# DC_MotorDriver_2Channel.net
KiCad netlist of a schematic drawn in Altium Designer
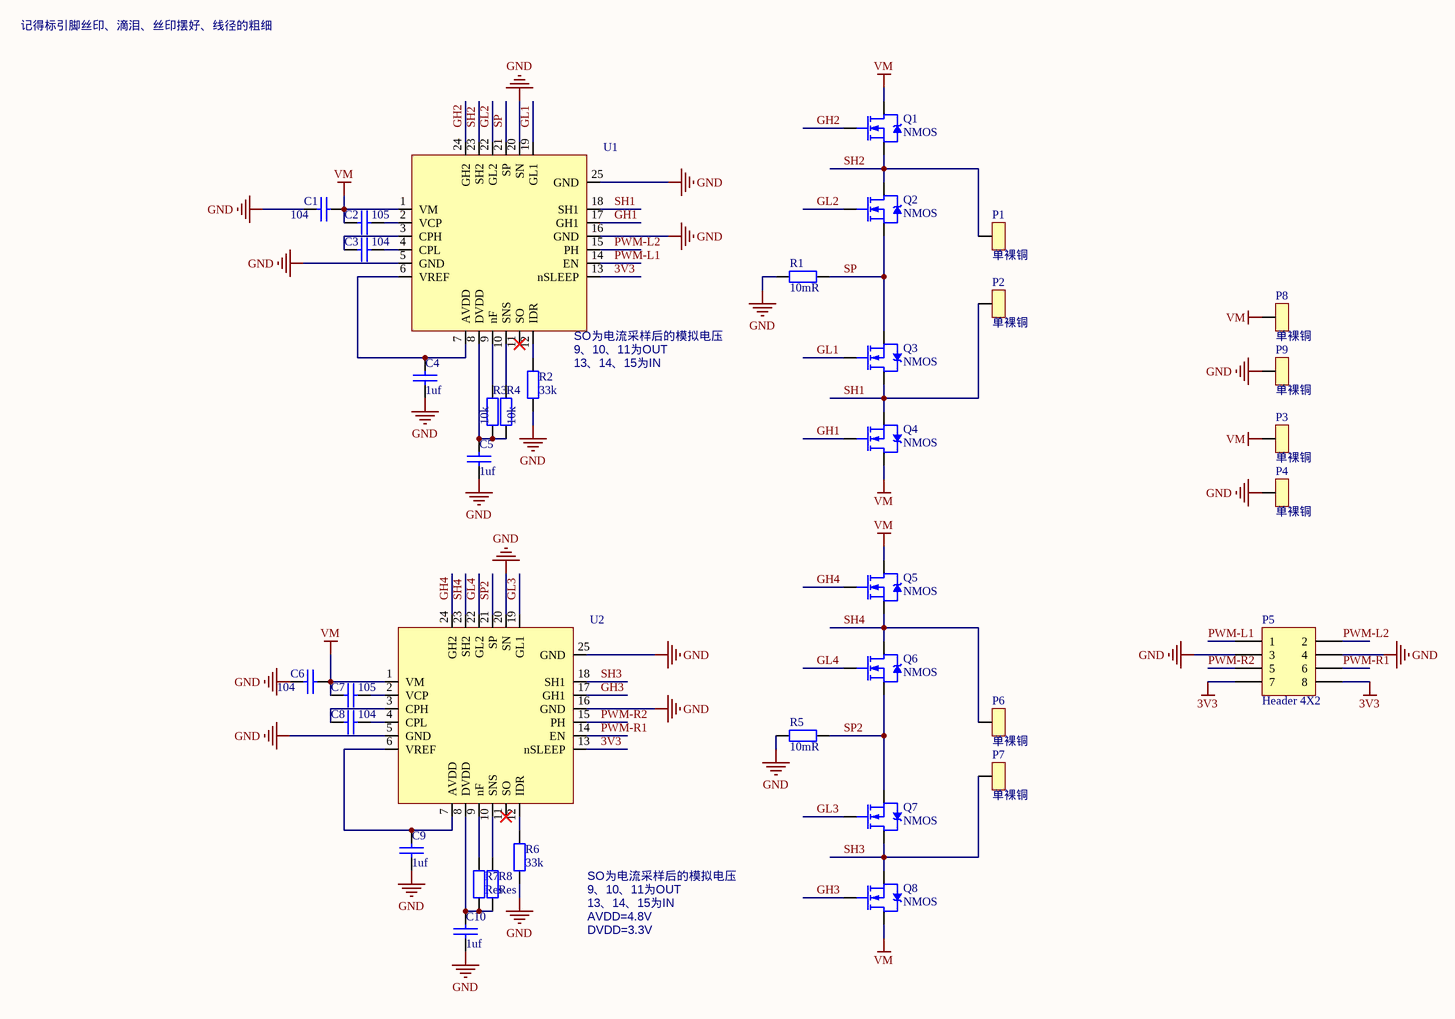
[diagram p0: DC_MotorDriver_2Channel.SchDoc]

(export (version "E")
  (design (tool "Eeschema 10.0.6"))
  (components
    (comp (ref "C1")
      (value "104")
      (footprint "0603C")
      (description "Capacitor")
      (libsource (lib "ywh") (part "CAP"))
    )
    (comp (ref "C2")
      (value "105")
      (footprint "0603C")
      (description "Capacitor")
      (libsource (lib "ywh") (part "CAP"))
    )
    (comp (ref "C3")
      (value "104")
      (footprint "0603C")
      (description "Capacitor")
      (libsource (lib "ywh") (part "CAP"))
    )
    (comp (ref "C4")
      (value "1uf")
      (footprint "0603C")
      (description "Capacitor")
      (libsource (lib "ywh") (part "CAP"))
    )
    (comp (ref "C5")
      (value "1uf")
      (footprint "0603C")
      (description "Capacitor")
      (libsource (lib "ywh") (part "CAP"))
    )
    (comp (ref "C6")
      (value "104")
      (footprint "0603C")
      (description "Capacitor")
      (libsource (lib "ywh") (part "CAP"))
    )
    (comp (ref "C7")
      (value "105")
      (footprint "0603C")
      (description "Capacitor")
      (libsource (lib "ywh") (part "CAP"))
    )
    (comp (ref "C8")
      (value "104")
      (footprint "0603C")
      (description "Capacitor")
      (libsource (lib "ywh") (part "CAP"))
    )
    (comp (ref "C9")
      (value "1uf")
      (footprint "0603C")
      (description "Capacitor")
      (libsource (lib "ywh") (part "CAP"))
    )
    (comp (ref "C10")
      (value "1uf")
      (footprint "0603C")
      (description "Capacitor")
      (libsource (lib "ywh") (part "CAP"))
    )
    (comp (ref "P1") (value "单裸铜") (footprint "裸铜2*5") (libsource (lib "ywh") (part "单裸铜")))
    (comp (ref "P2") (value "单裸铜") (footprint "裸铜2*5") (libsource (lib "ywh") (part "单裸铜")))
    (comp (ref "P3") (value "单裸铜") (footprint "裸铜2*5") (libsource (lib "ywh") (part "单裸铜")))
    (comp (ref "P4") (value "单裸铜") (footprint "裸铜2*5") (libsource (lib "ywh") (part "单裸铜")))
    (comp (ref "P5")
      (value "Header 4X2")
      (footprint "HDR2X4")
      (description "Header, 4-Pin, Dual row")
      (fields (field (name "PUBLISHER") "Altium Limited"))
      (libsource (lib "ywh") (part "Header 4X2"))
    )
    (comp (ref "P6") (value "单裸铜") (footprint "裸铜2*5") (libsource (lib "ywh") (part "单裸铜")))
    (comp (ref "P7") (value "单裸铜") (footprint "裸铜2*5") (libsource (lib "ywh") (part "单裸铜")))
    (comp (ref "P8") (value "单裸铜") (footprint "裸铜2*5") (libsource (lib "ywh") (part "单裸铜")))
    (comp (ref "P9") (value "单裸铜") (footprint "裸铜2*5") (libsource (lib "ywh") (part "单裸铜")))
    (comp (ref "Q1") (value "NMOS") (footprint "DNF5X6") (libsource (lib "ywh") (part "NMOS")))
    (comp (ref "Q2") (value "NMOS") (footprint "DNF5X6") (libsource (lib "ywh") (part "NMOS")))
    (comp (ref "Q3") (value "NMOS") (footprint "DNF5X6") (libsource (lib "ywh") (part "NMOS")))
    (comp (ref "Q4") (value "NMOS") (footprint "DNF5X6") (libsource (lib "ywh") (part "NMOS")))
    (comp (ref "Q5") (value "NMOS") (footprint "DNF5X6") (libsource (lib "ywh") (part "NMOS")))
    (comp (ref "Q6") (value "NMOS") (footprint "DNF5X6") (libsource (lib "ywh") (part "NMOS")))
    (comp (ref "Q7") (value "NMOS") (footprint "DNF5X6") (libsource (lib "ywh") (part "NMOS")))
    (comp (ref "Q8") (value "NMOS") (footprint "DNF5X6") (libsource (lib "ywh") (part "NMOS")))
    (comp (ref "R1")
      (value "10mR")
      (footprint "1206R")
      (description "Resistor")
      (libsource (lib "ywh") (part "Res"))
    )
    (comp (ref "R2")
      (value "33k")
      (footprint "0603R")
      (description "Resistor")
      (libsource (lib "") (part "Res_1"))
    )
    (comp (ref "R3")
      (value "10k")
      (footprint "0603R")
      (description "Resistor")
      (libsource (lib "") (part "Res_1"))
    )
    (comp (ref "R4")
      (value "10k")
      (footprint "0603R")
      (description "Resistor")
      (libsource (lib "") (part "Res_1"))
    )
    (comp (ref "R5")
      (value "10mR")
      (footprint "1206R")
      (description "Resistor")
      (libsource (lib "ywh") (part "Res"))
    )
    (comp (ref "R6")
      (value "33k")
      (footprint "0603R")
      (description "Resistor")
      (libsource (lib "") (part "Res_1"))
    )
    (comp (ref "R7")
      (value "Res")
      (footprint "0603R")
      (description "Resistor")
      (libsource (lib "") (part "Res_1"))
    )
    (comp (ref "R8")
      (value "Res")
      (footprint "0603R")
      (description "Resistor")
      (libsource (lib "") (part "Res_1"))
    )
    (comp (ref "U1") (value "DRV8701") (footprint "QFN24") (libsource (lib "ywh") (part "DRV8701")))
    (comp (ref "U2") (value "DRV8701") (footprint "QFN24") (libsource (lib "ywh") (part "DRV8701")))
  )
  (nets
    (net (code "1") (name "/GH1") (class "Default")
      (node (ref "Q4") (pin "1") (pinfunction "G_1") (pintype "passive"))
      (node (ref "U1") (pin "17") (pinfunction "GH1_17") (pintype "passive"))
    )
    (net (code "2") (name "/GH2") (class "Default")
      (node (ref "Q1") (pin "1") (pinfunction "G_1") (pintype "passive"))
      (node (ref "U1") (pin "24") (pinfunction "GH2_24") (pintype "passive"))
    )
    (net (code "3") (name "/GH3") (class "Default")
      (node (ref "Q8") (pin "1") (pinfunction "G_1") (pintype "passive"))
      (node (ref "U2") (pin "17") (pinfunction "GH1_17") (pintype "passive"))
    )
    (net (code "4") (name "/GH4") (class "Default")
      (node (ref "Q5") (pin "1") (pinfunction "G_1") (pintype "passive"))
      (node (ref "U2") (pin "24") (pinfunction "GH2_24") (pintype "passive"))
    )
    (net (code "5") (name "/GL1") (class "Default")
      (node (ref "Q3") (pin "1") (pinfunction "G_1") (pintype "passive"))
      (node (ref "U1") (pin "19") (pinfunction "GL1_19") (pintype "passive"))
    )
    (net (code "6") (name "/GL2") (class "Default")
      (node (ref "Q2") (pin "1") (pinfunction "G_1") (pintype "passive"))
      (node (ref "U1") (pin "22") (pinfunction "GL2_22") (pintype "passive"))
    )
    (net (code "7") (name "/GL3") (class "Default")
      (node (ref "Q7") (pin "1") (pinfunction "G_1") (pintype "passive"))
      (node (ref "U2") (pin "19") (pinfunction "GL1_19") (pintype "passive"))
    )
    (net (code "8") (name "/GL4") (class "Default")
      (node (ref "Q6") (pin "1") (pinfunction "G_1") (pintype "passive"))
      (node (ref "U2") (pin "22") (pinfunction "GL2_22") (pintype "passive"))
    )
    (net (code "9") (name "/PWM-L1") (class "Default")
      (node (ref "P5") (pin "1") (pinfunction "1_1") (pintype "passive"))
      (node (ref "U1") (pin "14") (pinfunction "EN_14") (pintype "passive"))
    )
    (net (code "10") (name "/PWM-L2") (class "Default")
      (node (ref "P5") (pin "2") (pinfunction "2_2") (pintype "passive"))
      (node (ref "U1") (pin "15") (pinfunction "PH_15") (pintype "passive"))
    )
    (net (code "11") (name "/PWM-R1") (class "Default")
      (node (ref "P5") (pin "6") (pinfunction "6_6") (pintype "passive"))
      (node (ref "U2") (pin "14") (pinfunction "EN_14") (pintype "passive"))
    )
    (net (code "12") (name "/PWM-R2") (class "Default")
      (node (ref "P5") (pin "5") (pinfunction "5_5") (pintype "passive"))
      (node (ref "U2") (pin "15") (pinfunction "PH_15") (pintype "passive"))
    )
    (net (code "13") (name "/SH1") (class "Default")
      (node (ref "P2") (pin "1") (pinfunction "1_1") (pintype "passive"))
      (node (ref "Q3") (pin "2") (pinfunction "D_2") (pintype "passive"))
      (node (ref "Q4") (pin "3") (pinfunction "S_3") (pintype "passive"))
      (node (ref "U1") (pin "18") (pinfunction "SH1_18") (pintype "passive"))
    )
    (net (code "14") (name "/SH2") (class "Default")
      (node (ref "P1") (pin "1") (pinfunction "1_1") (pintype "passive"))
      (node (ref "Q1") (pin "3") (pinfunction "S_3") (pintype "passive"))
      (node (ref "Q2") (pin "2") (pinfunction "D_2") (pintype "passive"))
      (node (ref "U1") (pin "23") (pinfunction "SH2_23") (pintype "passive"))
    )
    (net (code "15") (name "/SH3") (class "Default")
      (node (ref "P7") (pin "1") (pinfunction "1_1") (pintype "passive"))
      (node (ref "Q7") (pin "2") (pinfunction "D_2") (pintype "passive"))
      (node (ref "Q8") (pin "3") (pinfunction "S_3") (pintype "passive"))
      (node (ref "U2") (pin "18") (pinfunction "SH1_18") (pintype "passive"))
    )
    (net (code "16") (name "/SH4") (class "Default")
      (node (ref "P6") (pin "1") (pinfunction "1_1") (pintype "passive"))
      (node (ref "Q5") (pin "3") (pinfunction "S_3") (pintype "passive"))
      (node (ref "Q6") (pin "2") (pinfunction "D_2") (pintype "passive"))
      (node (ref "U2") (pin "23") (pinfunction "SH2_23") (pintype "passive"))
    )
    (net (code "17") (name "/SP") (class "Default")
      (node (ref "Q2") (pin "3") (pinfunction "S_3") (pintype "passive"))
      (node (ref "Q3") (pin "3") (pinfunction "S_3") (pintype "passive"))
      (node (ref "R1") (pin "1") (pinfunction "1_1") (pintype "passive"))
      (node (ref "U1") (pin "21") (pinfunction "SP_21") (pintype "passive"))
    )
    (net (code "18") (name "/SP2") (class "Default")
      (node (ref "Q6") (pin "3") (pinfunction "S_3") (pintype "passive"))
      (node (ref "Q7") (pin "3") (pinfunction "S_3") (pintype "passive"))
      (node (ref "R5") (pin "1") (pinfunction "1_1") (pintype "passive"))
      (node (ref "U2") (pin "21") (pinfunction "SP_21") (pintype "passive"))
    )
    (net (code "19") (name "3V3") (class "Default")
      (node (ref "P5") (pin "7") (pinfunction "7_7") (pintype "passive"))
      (node (ref "P5") (pin "8") (pinfunction "8_8") (pintype "passive"))
      (node (ref "U1") (pin "13") (pinfunction "nSLEEP_13") (pintype "passive"))
      (node (ref "U2") (pin "13") (pinfunction "nSLEEP_13") (pintype "passive"))
    )
    (net (code "20") (name "GND") (class "Default")
      (node (ref "C1") (pin "1") (pinfunction "1_1") (pintype "passive"))
      (node (ref "C10") (pin "1") (pinfunction "1_1") (pintype "passive"))
      (node (ref "C4") (pin "1") (pinfunction "1_1") (pintype "passive"))
      (node (ref "C5") (pin "1") (pinfunction "1_1") (pintype "passive"))
      (node (ref "C6") (pin "1") (pinfunction "1_1") (pintype "passive"))
      (node (ref "C9") (pin "1") (pinfunction "1_1") (pintype "passive"))
      (node (ref "P4") (pin "1") (pinfunction "1_1") (pintype "passive"))
      (node (ref "P5") (pin "3") (pinfunction "3_3") (pintype "passive"))
      (node (ref "P5") (pin "4") (pinfunction "4_4") (pintype "passive"))
      (node (ref "P9") (pin "1") (pinfunction "1_1") (pintype "passive"))
      (node (ref "R1") (pin "2") (pinfunction "2_2") (pintype "passive"))
      (node (ref "R2") (pin "2") (pinfunction "2_2") (pintype "passive"))
      (node (ref "R5") (pin "2") (pinfunction "2_2") (pintype "passive"))
      (node (ref "R6") (pin "2") (pinfunction "2_2") (pintype "passive"))
      (node (ref "U1") (pin "16") (pinfunction "GND_16") (pintype "passive"))
      (node (ref "U1") (pin "20") (pinfunction "SN_20") (pintype "passive"))
      (node (ref "U1") (pin "25") (pinfunction "GND_25") (pintype "passive"))
      (node (ref "U1") (pin "5") (pinfunction "GND_5") (pintype "passive"))
      (node (ref "U2") (pin "16") (pinfunction "GND_16") (pintype "passive"))
      (node (ref "U2") (pin "20") (pinfunction "SN_20") (pintype "passive"))
      (node (ref "U2") (pin "25") (pinfunction "GND_25") (pintype "passive"))
      (node (ref "U2") (pin "5") (pinfunction "GND_5") (pintype "passive"))
    )
    (net (code "21") (name "Net-(U1-AVDD)") (class "Default")
      (node (ref "C4") (pin "2") (pinfunction "2_2") (pintype "passive"))
      (node (ref "U1") (pin "6") (pinfunction "VREF_6") (pintype "passive"))
      (node (ref "U1") (pin "7") (pinfunction "AVDD_7") (pintype "passive"))
    )
    (net (code "22") (name "Net-(U1-CPH)") (class "Default")
      (node (ref "C3") (pin "1") (pinfunction "1_1") (pintype "passive"))
      (node (ref "U1") (pin "3") (pinfunction "CPH_3") (pintype "passive"))
    )
    (net (code "23") (name "Net-(U1-CPL)") (class "Default")
      (node (ref "C3") (pin "2") (pinfunction "2_2") (pintype "passive"))
      (node (ref "U1") (pin "4") (pinfunction "CPL_4") (pintype "passive"))
    )
    (net (code "24") (name "Net-(U1-DVDD)") (class "Default")
      (node (ref "C5") (pin "2") (pinfunction "2_2") (pintype "passive"))
      (node (ref "R3") (pin "2") (pinfunction "2_2") (pintype "passive"))
      (node (ref "R4") (pin "2") (pinfunction "2_2") (pintype "passive"))
      (node (ref "U1") (pin "8") (pinfunction "DVDD_8") (pintype "passive"))
    )
    (net (code "25") (name "Net-(U1-IDR)") (class "Default")
      (node (ref "R2") (pin "1") (pinfunction "1_1") (pintype "passive"))
      (node (ref "U1") (pin "12") (pinfunction "IDR_12") (pintype "passive"))
    )
    (net (code "26") (name "Net-(U1-SNS)") (class "Default")
      (node (ref "R4") (pin "1") (pinfunction "1_1") (pintype "passive"))
      (node (ref "U1") (pin "10") (pinfunction "SNS_10") (pintype "passive"))
    )
    (net (code "27") (name "Net-(U1-VCP)") (class "Default")
      (node (ref "C2") (pin "2") (pinfunction "2_2") (pintype "passive"))
      (node (ref "U1") (pin "2") (pinfunction "VCP_2") (pintype "passive"))
    )
    (net (code "28") (name "Net-(U1-nF)") (class "Default")
      (node (ref "R3") (pin "1") (pinfunction "1_1") (pintype "passive"))
      (node (ref "U1") (pin "9") (pinfunction "nF_9") (pintype "passive"))
    )
    (net (code "29") (name "Net-(U2-AVDD)") (class "Default")
      (node (ref "C9") (pin "2") (pinfunction "2_2") (pintype "passive"))
      (node (ref "U2") (pin "6") (pinfunction "VREF_6") (pintype "passive"))
      (node (ref "U2") (pin "7") (pinfunction "AVDD_7") (pintype "passive"))
    )
    (net (code "30") (name "Net-(U2-CPH)") (class "Default")
      (node (ref "C8") (pin "1") (pinfunction "1_1") (pintype "passive"))
      (node (ref "U2") (pin "3") (pinfunction "CPH_3") (pintype "passive"))
    )
    (net (code "31") (name "Net-(U2-CPL)") (class "Default")
      (node (ref "C8") (pin "2") (pinfunction "2_2") (pintype "passive"))
      (node (ref "U2") (pin "4") (pinfunction "CPL_4") (pintype "passive"))
    )
    (net (code "32") (name "Net-(U2-DVDD)") (class "Default")
      (node (ref "C10") (pin "2") (pinfunction "2_2") (pintype "passive"))
      (node (ref "R7") (pin "2") (pinfunction "2_2") (pintype "passive"))
      (node (ref "R8") (pin "2") (pinfunction "2_2") (pintype "passive"))
      (node (ref "U2") (pin "8") (pinfunction "DVDD_8") (pintype "passive"))
    )
    (net (code "33") (name "Net-(U2-IDR)") (class "Default")
      (node (ref "R6") (pin "1") (pinfunction "1_1") (pintype "passive"))
      (node (ref "U2") (pin "12") (pinfunction "IDR_12") (pintype "passive"))
    )
    (net (code "34") (name "Net-(U2-SNS)") (class "Default")
      (node (ref "R8") (pin "1") (pinfunction "1_1") (pintype "passive"))
      (node (ref "U2") (pin "10") (pinfunction "SNS_10") (pintype "passive"))
    )
    (net (code "35") (name "Net-(U2-VCP)") (class "Default")
      (node (ref "C7") (pin "2") (pinfunction "2_2") (pintype "passive"))
      (node (ref "U2") (pin "2") (pinfunction "VCP_2") (pintype "passive"))
    )
    (net (code "36") (name "Net-(U2-nF)") (class "Default")
      (node (ref "R7") (pin "1") (pinfunction "1_1") (pintype "passive"))
      (node (ref "U2") (pin "9") (pinfunction "nF_9") (pintype "passive"))
    )
    (net (code "37") (name "VM") (class "Default")
      (node (ref "C1") (pin "2") (pinfunction "2_2") (pintype "passive"))
      (node (ref "C2") (pin "1") (pinfunction "1_1") (pintype "passive"))
      (node (ref "C6") (pin "2") (pinfunction "2_2") (pintype "passive"))
      (node (ref "C7") (pin "1") (pinfunction "1_1") (pintype "passive"))
      (node (ref "P3") (pin "1") (pinfunction "1_1") (pintype "passive"))
      (node (ref "P8") (pin "1") (pinfunction "1_1") (pintype "passive"))
      (node (ref "Q1") (pin "2") (pinfunction "D_2") (pintype "passive"))
      (node (ref "Q4") (pin "2") (pinfunction "D_2") (pintype "passive"))
      (node (ref "Q5") (pin "2") (pinfunction "D_2") (pintype "passive"))
      (node (ref "Q8") (pin "2") (pinfunction "D_2") (pintype "passive"))
      (node (ref "U1") (pin "1") (pinfunction "VM_1") (pintype "passive"))
      (node (ref "U2") (pin "1") (pinfunction "VM_1") (pintype "passive"))
    )
    (net (code "38") (name "unconnected-(U1-SO-Pad11)") (class "Default")
      (node (ref "U1") (pin "11") (pinfunction "SO_11") (pintype "passive+no_connect"))
    )
    (net (code "39") (name "unconnected-(U2-SO-Pad11)") (class "Default")
      (node (ref "U2") (pin "11") (pinfunction "SO_11") (pintype "passive+no_connect"))
    )
  )
)
